# Sheet1.net
KiCad netlist of a schematic drawn in Altium Designer
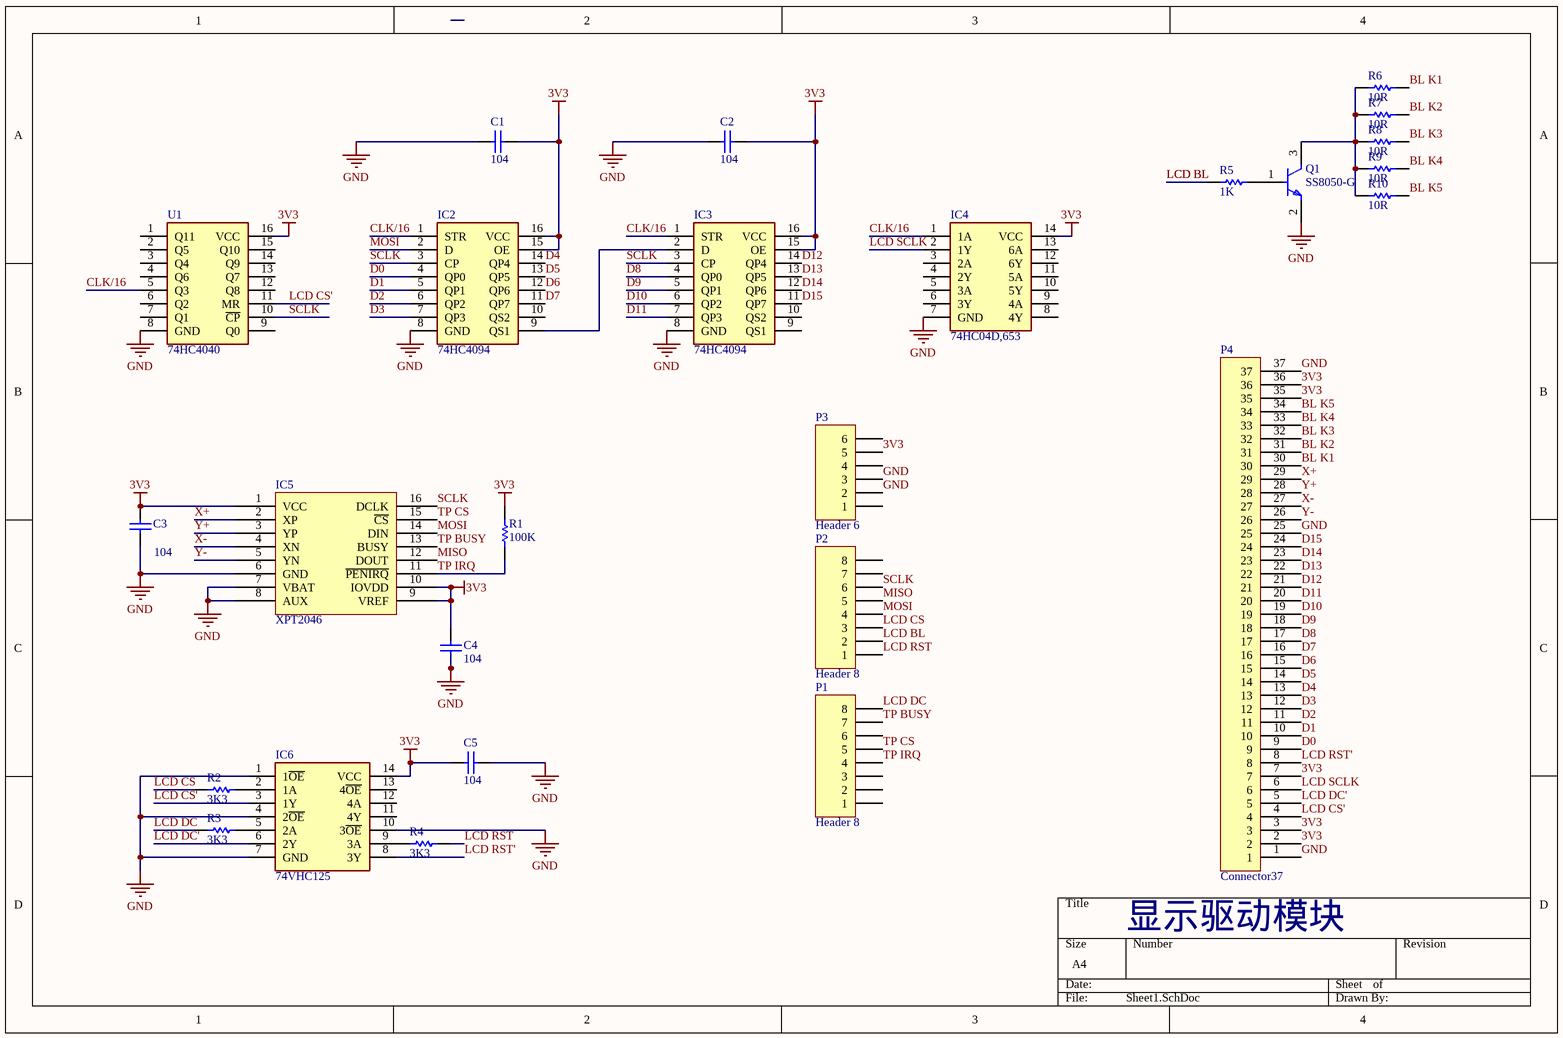
[diagram p0: Sheet1.SchDoc]

(export (version "E")
  (design (tool "Eeschema 10.0.6"))
  (components
    (comp (ref "C1")
      (value "104")
      (footprint "CAPC2013X135X45LL10T25")
      (fields (field (name "MANUFACTURER") "Murata") (field (name "PART NUMBER") "GRM21BR72E103KW03L"))
      (libsource (lib "Altium Content Vault") (part "CAP"))
    )
    (comp (ref "C2")
      (value "104")
      (footprint "CAPC2013X135X45LL10T25")
      (fields (field (name "MANUFACTURER") "Murata") (field (name "PART NUMBER") "GRM21BR72E103KW03L"))
      (libsource (lib "Altium Content Vault") (part "CAP"))
    )
    (comp (ref "C3")
      (value "104")
      (footprint "CAPC2013X135X45LL10T25")
      (fields (field (name "MANUFACTURER") "Murata") (field (name "PART NUMBER") "GRM21BR72E103KW03L"))
      (libsource (lib "Altium Content Vault") (part "CAP"))
    )
    (comp (ref "C4")
      (value "104")
      (footprint "CAPC2013X135X45LL10T25")
      (fields (field (name "MANUFACTURER") "Murata") (field (name "PART NUMBER") "GRM21BR72E103KW03L"))
      (libsource (lib "Altium Content Vault") (part "CAP"))
    )
    (comp (ref "C5")
      (value "104")
      (footprint "CAPC2013X135X45LL10T25")
      (fields (field (name "MANUFACTURER") "Murata") (field (name "PART NUMBER") "GRM21BR72E103KW03L"))
      (libsource (lib "Altium Content Vault") (part "CAP"))
    )
    (comp (ref "IC2")
      (value "74HC4094")
      (footprint "SamacSys:74HC4094D653")
      (description "Integrated Circuit")
      (fields
        (field (name "MANUFACTURER_PART_NUMBER") "74HC4094D,653")
        (field (name "MOUSER PART NUMBER") "771-74HC4094D-T")
      )
      (libsource (lib "*") (part "74HC4094D,653"))
    )
    (comp (ref "IC3")
      (value "74HC4094")
      (footprint "SamacSys:74HC4094D653")
      (description "Integrated Circuit")
      (fields
        (field (name "MANUFACTURER_PART_NUMBER") "74HC4094D,653")
        (field (name "MOUSER PART NUMBER") "771-74HC4094D-T")
      )
      (libsource (lib "*") (part "74HC4094D,653"))
    )
    (comp (ref "IC4")
      (value "74HC04D,653")
      (footprint "SamacSys:SOIC127P600X175-14N")
      (description "Integrated Circuit")
      (fields (field (name "MOUSER PART NUMBER") "771-74HC04D-T"))
      (libsource (lib "*") (part "74HC04D,653"))
    )
    (comp (ref "IC5")
      (value "XPT2046")
      (footprint "TSOP65P640X110-16N")
      (libsource (lib "Schlib1") (part "XPT2046"))
    )
    (comp (ref "IC6")
      (value "74VHC125")
      (footprint "SOP65P640X510-14N")
      (description "Integrated Circuit")
      (fields
        (field (name "MANUFACTURER_PART_NUMBER") "74VHC125D,118")
        (field (name "MOUSER PART NUMBER") "771-74VHC125D118")
      )
      (libsource (lib "*") (part "74VHC125D,118"))
    )
    (comp (ref "P1")
      (value "Header 8")
      (footprint "HDR1X8")
      (description "Header, 8-Pin")
      (fields (field (name "PUBLISHER") "Altium Limited"))
      (libsource (lib "Miscellaneous Connectors") (part "Header 8"))
    )
    (comp (ref "P2")
      (value "Header 8")
      (footprint "HDR1X8")
      (description "Header, 8-Pin")
      (fields (field (name "PUBLISHER") "Altium Limited"))
      (libsource (lib "Miscellaneous Connectors") (part "Header 8"))
    )
    (comp (ref "P3")
      (value "Header 6")
      (footprint "HDR1X6")
      (description "Header, 6-Pin")
      (fields (field (name "PUBLISHER") "Altium Limited"))
      (libsource (lib "Miscellaneous Connectors") (part "Header 6"))
    )
    (comp (ref "P4") (value "Connector37") (footprint "C37") (libsource (lib "Schlib1") (part "Connector37")))
    (comp (ref "Q1")
      (value "SS8050-G")
      (footprint "FP-SS8050-G-MFG")
      (description "NPN TRANSISTOR 1.5A 40V SOT-23 R")
      (libsource (lib "Altium Content Vault") (part "2a1388f82443b098dcd57d24ac7632d"))
    )
    (comp (ref "R1")
      (value "100K")
      (footprint "RESC2013X60X35ML10T20")
      (description "Chip Resistor, 100 KOhm, +/- 1%, 0.125 W, -55 to 155 degC, 0805 (2012 Metric), RoHS, Tape and Reel")
      (fields (field (name "MANUFACTURER") "Yageo") (field (name "TOLERANCE") "1%"))
      (libsource (lib "Altium Content Vault") (part "RES-2"))
    )
    (comp (ref "R2")
      (value "3K3")
      (footprint "RESC2013X60X35ML10T20")
      (description "Chip Resistor, 1 KOhm, +/- 1%, 125 mW, -55 to 155 degC, 0805 (2012 Metric), RoHS, Tape and Reel")
      (fields (field (name "TOLERANCE") "1%") (field (name "MANUFACTURER") "Yageo"))
      (libsource (lib "Altium Content Vault") (part "RES-2"))
    )
    (comp (ref "R3")
      (value "3K3")
      (footprint "RESC2013X60X35ML10T20")
      (description "Chip Resistor, 1 KOhm, +/- 1%, 125 mW, -55 to 155 degC, 0805 (2012 Metric), RoHS, Tape and Reel")
      (fields (field (name "TOLERANCE") "1%") (field (name "MANUFACTURER") "Yageo"))
      (libsource (lib "Altium Content Vault") (part "RES-2"))
    )
    (comp (ref "R4")
      (value "3K3")
      (footprint "RESC2013X60X35ML10T20")
      (description "Chip Resistor, 1 KOhm, +/- 1%, 125 mW, -55 to 155 degC, 0805 (2012 Metric), RoHS, Tape and Reel")
      (fields (field (name "TOLERANCE") "1%") (field (name "MANUFACTURER") "Yageo"))
      (libsource (lib "Altium Content Vault") (part "RES-2"))
    )
    (comp (ref "R5")
      (value "1K")
      (footprint "RESC2013X60X35ML10T20")
      (description "Chip Resistor, 1 KOhm, +/- 1%, 125 mW, -55 to 155 degC, 0805 (2012 Metric), RoHS, Tape and Reel")
      (fields (field (name "TOLERANCE") "1%") (field (name "MANUFACTURER") "Yageo"))
      (libsource (lib "Altium Content Vault") (part "RES-2"))
    )
    (comp (ref "R6")
      (value "10R")
      (footprint "RESC2013X60X35ML10T20")
      (description "Chip Resistor, 10 Ohm, +/- 1%, 0.125 W, -55 to 155 degC, 0805 (2012 Metric), RoHS, Tape and Reel")
      (fields (field (name "MANUFACTURER") "Yageo") (field (name "TOLERANCE") "1%"))
      (libsource (lib "Altium Content Vault") (part "RES-2"))
    )
    (comp (ref "R7")
      (value "10R")
      (footprint "RESC2013X60X35ML10T20")
      (description "Chip Resistor, 10 Ohm, +/- 1%, 0.125 W, -55 to 155 degC, 0805 (2012 Metric), RoHS, Tape and Reel")
      (fields (field (name "MANUFACTURER") "Yageo") (field (name "TOLERANCE") "1%"))
      (libsource (lib "Altium Content Vault") (part "RES-2"))
    )
    (comp (ref "R8")
      (value "10R")
      (footprint "RESC2013X60X35ML10T20")
      (description "Chip Resistor, 10 Ohm, +/- 1%, 0.125 W, -55 to 155 degC, 0805 (2012 Metric), RoHS, Tape and Reel")
      (fields (field (name "MANUFACTURER") "Yageo") (field (name "TOLERANCE") "1%"))
      (libsource (lib "Altium Content Vault") (part "RES-2"))
    )
    (comp (ref "R9")
      (value "10R")
      (footprint "RESC2013X60X35ML10T20")
      (description "Chip Resistor, 10 Ohm, +/- 1%, 0.125 W, -55 to 155 degC, 0805 (2012 Metric), RoHS, Tape and Reel")
      (fields (field (name "MANUFACTURER") "Yageo") (field (name "TOLERANCE") "1%"))
      (libsource (lib "Altium Content Vault") (part "RES-2"))
    )
    (comp (ref "R10")
      (value "10R")
      (footprint "RESC2013X60X35ML10T20")
      (description "Chip Resistor, 10 Ohm, +/- 1%, 0.125 W, -55 to 155 degC, 0805 (2012 Metric), RoHS, Tape and Reel")
      (fields (field (name "MANUFACTURER") "Yageo") (field (name "TOLERANCE") "1%"))
      (libsource (lib "Altium Content Vault") (part "RES-2"))
    )
    (comp (ref "U1")
      (value "74HC4040")
      (footprint "SamacSys:74HC4040D653")
      (description "Integrated Circuit")
      (fields
        (field (name "MANUFACTURER_PART_NUMBER") "74HC4040D,653")
        (field (name "MOUSER PART NUMBER") "771-74HC4040D-T")
      )
      (libsource (lib "*") (part "74HC4040D,653"))
    )
  )
  (nets
    (net (code "1") (name "/BL K1") (class "Default")
      (node (ref "P4") (pin "30") (pinfunction "30_30") (pintype "open_emitter"))
      (node (ref "R6") (pin "2") (pinfunction "2_2") (pintype "passive"))
    )
    (net (code "2") (name "/BL K2") (class "Default")
      (node (ref "P4") (pin "31") (pinfunction "31_31") (pintype "open_emitter"))
      (node (ref "R7") (pin "2") (pinfunction "2_2") (pintype "passive"))
    )
    (net (code "3") (name "/BL K3") (class "Default")
      (node (ref "P4") (pin "32") (pinfunction "32_32") (pintype "open_emitter"))
      (node (ref "R8") (pin "2") (pinfunction "2_2") (pintype "passive"))
    )
    (net (code "4") (name "/BL K4") (class "Default")
      (node (ref "P4") (pin "33") (pinfunction "33_33") (pintype "open_emitter"))
      (node (ref "R9") (pin "2") (pinfunction "2_2") (pintype "passive"))
    )
    (net (code "5") (name "/BL K5") (class "Default")
      (node (ref "P4") (pin "34") (pinfunction "34_34") (pintype "open_emitter"))
      (node (ref "R10") (pin "2") (pinfunction "2_2") (pintype "passive"))
    )
    (net (code "6") (name "/CLK{slash}16") (class "Default")
      (node (ref "IC2") (pin "1") (pinfunction "STR_1") (pintype "passive"))
      (node (ref "IC3") (pin "1") (pinfunction "STR_1") (pintype "passive"))
      (node (ref "IC4") (pin "1") (pinfunction "1A_1") (pintype "passive"))
      (node (ref "U1") (pin "5") (pinfunction "Q3_5") (pintype "passive"))
    )
    (net (code "7") (name "/D0") (class "Default")
      (node (ref "IC2") (pin "4") (pinfunction "QP0_4") (pintype "passive"))
      (node (ref "P4") (pin "9") (pinfunction "9_9") (pintype "open_emitter"))
    )
    (net (code "8") (name "/D1") (class "Default")
      (node (ref "IC2") (pin "5") (pinfunction "QP1_5") (pintype "passive"))
      (node (ref "P4") (pin "10") (pinfunction "10_10") (pintype "open_emitter"))
    )
    (net (code "9") (name "/D2") (class "Default")
      (node (ref "IC2") (pin "6") (pinfunction "QP2_6") (pintype "passive"))
      (node (ref "P4") (pin "11") (pinfunction "11_11") (pintype "open_emitter"))
    )
    (net (code "10") (name "/D3") (class "Default")
      (node (ref "IC2") (pin "7") (pinfunction "QP3_7") (pintype "passive"))
      (node (ref "P4") (pin "12") (pinfunction "12_12") (pintype "open_emitter"))
    )
    (net (code "11") (name "/D4") (class "Default")
      (node (ref "IC2") (pin "14") (pinfunction "QP4_14") (pintype "passive"))
      (node (ref "P4") (pin "13") (pinfunction "13_13") (pintype "open_emitter"))
    )
    (net (code "12") (name "/D5") (class "Default")
      (node (ref "IC2") (pin "13") (pinfunction "QP5_13") (pintype "passive"))
      (node (ref "P4") (pin "14") (pinfunction "14_14") (pintype "open_emitter"))
    )
    (net (code "13") (name "/D6") (class "Default")
      (node (ref "IC2") (pin "12") (pinfunction "QP6_12") (pintype "passive"))
      (node (ref "P4") (pin "15") (pinfunction "15_15") (pintype "open_emitter"))
    )
    (net (code "14") (name "/D7") (class "Default")
      (node (ref "IC2") (pin "11") (pinfunction "QP7_11") (pintype "passive"))
      (node (ref "P4") (pin "16") (pinfunction "16_16") (pintype "open_emitter"))
    )
    (net (code "15") (name "/D8") (class "Default")
      (node (ref "IC3") (pin "4") (pinfunction "QP0_4") (pintype "passive"))
      (node (ref "P4") (pin "17") (pinfunction "17_17") (pintype "open_emitter"))
    )
    (net (code "16") (name "/D9") (class "Default")
      (node (ref "IC3") (pin "5") (pinfunction "QP1_5") (pintype "passive"))
      (node (ref "P4") (pin "18") (pinfunction "18_18") (pintype "open_emitter"))
    )
    (net (code "17") (name "/D10") (class "Default")
      (node (ref "IC3") (pin "6") (pinfunction "QP2_6") (pintype "passive"))
      (node (ref "P4") (pin "19") (pinfunction "19_19") (pintype "open_emitter"))
    )
    (net (code "18") (name "/D11") (class "Default")
      (node (ref "IC3") (pin "7") (pinfunction "QP3_7") (pintype "passive"))
      (node (ref "P4") (pin "20") (pinfunction "20_20") (pintype "open_emitter"))
    )
    (net (code "19") (name "/D12") (class "Default")
      (node (ref "IC3") (pin "14") (pinfunction "QP4_14") (pintype "passive"))
      (node (ref "P4") (pin "21") (pinfunction "21_21") (pintype "open_emitter"))
    )
    (net (code "20") (name "/D13") (class "Default")
      (node (ref "IC3") (pin "13") (pinfunction "QP5_13") (pintype "passive"))
      (node (ref "P4") (pin "22") (pinfunction "22_22") (pintype "open_emitter"))
    )
    (net (code "21") (name "/D14") (class "Default")
      (node (ref "IC3") (pin "12") (pinfunction "QP6_12") (pintype "passive"))
      (node (ref "P4") (pin "23") (pinfunction "23_23") (pintype "open_emitter"))
    )
    (net (code "22") (name "/D15") (class "Default")
      (node (ref "IC3") (pin "11") (pinfunction "QP7_11") (pintype "passive"))
      (node (ref "P4") (pin "24") (pinfunction "24_24") (pintype "open_emitter"))
    )
    (net (code "23") (name "/LCD BL") (class "Default")
      (node (ref "P2") (pin "2") (pinfunction "2_2") (pintype "passive"))
      (node (ref "R5") (pin "1") (pinfunction "1_1") (pintype "passive"))
    )
    (net (code "24") (name "/LCD CS") (class "Default")
      (node (ref "P2") (pin "3") (pinfunction "3_3") (pintype "passive"))
      (node (ref "R2") (pin "1") (pinfunction "1_1") (pintype "passive"))
    )
    (net (code "25") (name "/LCD CS'") (class "Default")
      (node (ref "IC6") (pin "3") (pinfunction "1Y_3") (pintype "passive"))
      (node (ref "P4") (pin "4") (pinfunction "4_4") (pintype "open_emitter"))
      (node (ref "U1") (pin "11") (pinfunction "MR_11") (pintype "passive"))
    )
    (net (code "26") (name "/LCD DC") (class "Default")
      (node (ref "P1") (pin "8") (pinfunction "8_8") (pintype "passive"))
      (node (ref "R3") (pin "1") (pinfunction "1_1") (pintype "passive"))
    )
    (net (code "27") (name "/LCD DC'") (class "Default")
      (node (ref "IC6") (pin "6") (pinfunction "2Y_6") (pintype "passive"))
      (node (ref "P4") (pin "5") (pinfunction "5_5") (pintype "open_emitter"))
    )
    (net (code "28") (name "/LCD RST") (class "Default")
      (node (ref "P2") (pin "1") (pinfunction "1_1") (pintype "passive"))
      (node (ref "R4") (pin "2") (pinfunction "2_2") (pintype "passive"))
    )
    (net (code "29") (name "/LCD RST'") (class "Default")
      (node (ref "IC6") (pin "8") (pinfunction "3Y_8") (pintype "passive"))
      (node (ref "P4") (pin "8") (pinfunction "8_8") (pintype "open_emitter"))
    )
    (net (code "30") (name "/LCD SCLK") (class "Default")
      (node (ref "IC4") (pin "2") (pinfunction "1Y_2") (pintype "passive"))
      (node (ref "P4") (pin "6") (pinfunction "6_6") (pintype "open_emitter"))
    )
    (net (code "31") (name "/MISO") (class "Default")
      (node (ref "IC5") (pin "12") (pinfunction "DOUT_12") (pintype "open_emitter"))
      (node (ref "P2") (pin "5") (pinfunction "5_5") (pintype "passive"))
    )
    (net (code "32") (name "/MOSI") (class "Default")
      (node (ref "IC2") (pin "2") (pinfunction "D_2") (pintype "passive"))
      (node (ref "IC5") (pin "14") (pinfunction "DIN_14") (pintype "open_emitter"))
      (node (ref "P2") (pin "4") (pinfunction "4_4") (pintype "passive"))
    )
    (net (code "33") (name "/SCLK") (class "Default")
      (node (ref "IC2") (pin "3") (pinfunction "CP_3") (pintype "passive"))
      (node (ref "IC3") (pin "3") (pinfunction "CP_3") (pintype "passive"))
      (node (ref "IC5") (pin "16") (pinfunction "DCLK_16") (pintype "open_emitter"))
      (node (ref "P2") (pin "6") (pinfunction "6_6") (pintype "passive"))
      (node (ref "U1") (pin "10") (pinfunction "~{CP}_10") (pintype "passive"))
    )
    (net (code "34") (name "/TP BUSY") (class "Default")
      (node (ref "IC5") (pin "13") (pinfunction "BUSY_13") (pintype "open_emitter"))
      (node (ref "P1") (pin "7") (pinfunction "7_7") (pintype "passive"))
    )
    (net (code "35") (name "/TP CS") (class "Default")
      (node (ref "IC5") (pin "15") (pinfunction "~{CS}_15") (pintype "open_emitter"))
      (node (ref "P1") (pin "5") (pinfunction "5_5") (pintype "passive"))
    )
    (net (code "36") (name "/TP IRQ") (class "Default")
      (node (ref "IC5") (pin "11") (pinfunction "~{PENIRQ}_11") (pintype "open_emitter"))
      (node (ref "P1") (pin "4") (pinfunction "4_4") (pintype "passive"))
      (node (ref "R1") (pin "2") (pinfunction "2_2") (pintype "passive"))
    )
    (net (code "37") (name "/X+") (class "Default")
      (node (ref "IC5") (pin "2") (pinfunction "XP_2") (pintype "open_emitter"))
      (node (ref "P4") (pin "29") (pinfunction "29_29") (pintype "open_emitter"))
    )
    (net (code "38") (name "/X-") (class "Default")
      (node (ref "IC5") (pin "4") (pinfunction "XN_4") (pintype "open_emitter"))
      (node (ref "P4") (pin "27") (pinfunction "27_27") (pintype "open_emitter"))
    )
    (net (code "39") (name "/Y+") (class "Default")
      (node (ref "IC5") (pin "3") (pinfunction "YP_3") (pintype "open_emitter"))
      (node (ref "P4") (pin "28") (pinfunction "28_28") (pintype "open_emitter"))
    )
    (net (code "40") (name "/Y-") (class "Default")
      (node (ref "IC5") (pin "5") (pinfunction "YN_5") (pintype "open_emitter"))
      (node (ref "P4") (pin "26") (pinfunction "26_26") (pintype "open_emitter"))
    )
    (net (code "41") (name "3V3") (class "Default")
      (node (ref "C1") (pin "2") (pinfunction "2_2") (pintype "passive"))
      (node (ref "C2") (pin "2") (pinfunction "2_2") (pintype "passive"))
      (node (ref "C3") (pin "1") (pinfunction "1_1") (pintype "passive"))
      (node (ref "C4") (pin "1") (pinfunction "1_1") (pintype "passive"))
      (node (ref "C5") (pin "1") (pinfunction "1_1") (pintype "passive"))
      (node (ref "IC2") (pin "15") (pinfunction "OE_15") (pintype "passive"))
      (node (ref "IC2") (pin "16") (pinfunction "VCC_16") (pintype "passive"))
      (node (ref "IC3") (pin "15") (pinfunction "OE_15") (pintype "passive"))
      (node (ref "IC3") (pin "16") (pinfunction "VCC_16") (pintype "passive"))
      (node (ref "IC4") (pin "14") (pinfunction "VCC_14") (pintype "passive"))
      (node (ref "IC5") (pin "1") (pinfunction "VCC_1") (pintype "open_emitter"))
      (node (ref "IC5") (pin "10") (pinfunction "IOVDD_10") (pintype "open_emitter"))
      (node (ref "IC5") (pin "9") (pinfunction "VREF_9") (pintype "open_emitter"))
      (node (ref "IC6") (pin "14") (pinfunction "VCC_14") (pintype "passive"))
      (node (ref "P3") (pin "5") (pinfunction "5_5") (pintype "passive"))
      (node (ref "P4") (pin "2") (pinfunction "2_2") (pintype "open_emitter"))
      (node (ref "P4") (pin "3") (pinfunction "3_3") (pintype "open_emitter"))
      (node (ref "P4") (pin "35") (pinfunction "35_35") (pintype "open_emitter"))
      (node (ref "P4") (pin "36") (pinfunction "36_36") (pintype "open_emitter"))
      (node (ref "P4") (pin "7") (pinfunction "7_7") (pintype "open_emitter"))
      (node (ref "R1") (pin "1") (pinfunction "1_1") (pintype "passive"))
      (node (ref "U1") (pin "16") (pinfunction "VCC_16") (pintype "passive"))
    )
    (net (code "42") (name "GND") (class "Default")
      (node (ref "C1") (pin "1") (pinfunction "1_1") (pintype "passive"))
      (node (ref "C2") (pin "1") (pinfunction "1_1") (pintype "passive"))
      (node (ref "C3") (pin "2") (pinfunction "2_2") (pintype "passive"))
      (node (ref "C4") (pin "2") (pinfunction "2_2") (pintype "passive"))
      (node (ref "C5") (pin "2") (pinfunction "2_2") (pintype "passive"))
      (node (ref "IC2") (pin "8") (pinfunction "GND_8") (pintype "passive"))
      (node (ref "IC3") (pin "8") (pinfunction "GND_8") (pintype "passive"))
      (node (ref "IC4") (pin "7") (pinfunction "GND_7") (pintype "passive"))
      (node (ref "IC5") (pin "6") (pinfunction "GND_6") (pintype "open_emitter"))
      (node (ref "IC5") (pin "7") (pinfunction "VBAT_7") (pintype "open_emitter"))
      (node (ref "IC5") (pin "8") (pinfunction "AUX_8") (pintype "open_emitter"))
      (node (ref "IC6") (pin "1") (pinfunction "1~{OE}_1") (pintype "passive"))
      (node (ref "IC6") (pin "10") (pinfunction "3~{OE}_10") (pintype "passive"))
      (node (ref "IC6") (pin "4") (pinfunction "2~{OE}_4") (pintype "passive"))
      (node (ref "IC6") (pin "7") (pinfunction "GND_7") (pintype "passive"))
      (node (ref "P3") (pin "2") (pinfunction "2_2") (pintype "passive"))
      (node (ref "P3") (pin "3") (pinfunction "3_3") (pintype "passive"))
      (node (ref "P4") (pin "1") (pinfunction "1_1") (pintype "open_emitter"))
      (node (ref "P4") (pin "25") (pinfunction "25_25") (pintype "open_emitter"))
      (node (ref "P4") (pin "37") (pinfunction "37_37") (pintype "open_emitter"))
      (node (ref "Q1") (pin "2") (pinfunction "E_2") (pintype "passive"))
      (node (ref "U1") (pin "8") (pinfunction "GND_8") (pintype "passive"))
    )
    (net (code "43") (name "Net-(IC2-QS1)") (class "Default")
      (node (ref "IC2") (pin "9") (pinfunction "QS1_9") (pintype "passive"))
      (node (ref "IC3") (pin "2") (pinfunction "D_2") (pintype "passive"))
    )
    (net (code "44") (name "Net-(IC6-1A)") (class "Default")
      (node (ref "IC6") (pin "2") (pinfunction "1A_2") (pintype "passive"))
      (node (ref "R2") (pin "2") (pinfunction "2_2") (pintype "passive"))
    )
    (net (code "45") (name "Net-(IC6-2A)") (class "Default")
      (node (ref "IC6") (pin "5") (pinfunction "2A_5") (pintype "passive"))
      (node (ref "R3") (pin "2") (pinfunction "2_2") (pintype "passive"))
    )
    (net (code "46") (name "Net-(IC6-3A)") (class "Default")
      (node (ref "IC6") (pin "9") (pinfunction "3A_9") (pintype "passive"))
      (node (ref "R4") (pin "1") (pinfunction "1_1") (pintype "passive"))
    )
    (net (code "47") (name "Net-(Q1-B)") (class "Default")
      (node (ref "Q1") (pin "1") (pinfunction "B_1") (pintype "passive"))
      (node (ref "R5") (pin "2") (pinfunction "2_2") (pintype "passive"))
    )
    (net (code "48") (name "Net-(Q1-C)") (class "Default")
      (node (ref "Q1") (pin "3") (pinfunction "C_3") (pintype "passive"))
      (node (ref "R10") (pin "1") (pinfunction "1_1") (pintype "passive"))
      (node (ref "R6") (pin "1") (pinfunction "1_1") (pintype "passive"))
      (node (ref "R7") (pin "1") (pinfunction "1_1") (pintype "passive"))
      (node (ref "R8") (pin "1") (pinfunction "1_1") (pintype "passive"))
      (node (ref "R9") (pin "1") (pinfunction "1_1") (pintype "passive"))
    )
    (net (code "49") (name "unconnected-(IC2-QS2-Pad10)") (class "Default")
      (node (ref "IC2") (pin "10") (pinfunction "QS2_10") (pintype "passive"))
    )
    (net (code "50") (name "unconnected-(IC3-QS1-Pad9)") (class "Default")
      (node (ref "IC3") (pin "9") (pinfunction "QS1_9") (pintype "passive"))
    )
    (net (code "51") (name "unconnected-(IC3-QS2-Pad10)") (class "Default")
      (node (ref "IC3") (pin "10") (pinfunction "QS2_10") (pintype "passive"))
    )
    (net (code "52") (name "unconnected-(IC4-2A-Pad3)") (class "Default")
      (node (ref "IC4") (pin "3") (pinfunction "2A_3") (pintype "passive"))
    )
    (net (code "53") (name "unconnected-(IC4-2Y-Pad4)") (class "Default")
      (node (ref "IC4") (pin "4") (pinfunction "2Y_4") (pintype "passive"))
    )
    (net (code "54") (name "unconnected-(IC4-3A-Pad5)") (class "Default")
      (node (ref "IC4") (pin "5") (pinfunction "3A_5") (pintype "passive"))
    )
    (net (code "55") (name "unconnected-(IC4-3Y-Pad6)") (class "Default")
      (node (ref "IC4") (pin "6") (pinfunction "3Y_6") (pintype "passive"))
    )
    (net (code "56") (name "unconnected-(IC4-4A-Pad9)") (class "Default")
      (node (ref "IC4") (pin "9") (pinfunction "4A_9") (pintype "passive"))
    )
    (net (code "57") (name "unconnected-(IC4-4Y-Pad8)") (class "Default")
      (node (ref "IC4") (pin "8") (pinfunction "4Y_8") (pintype "passive"))
    )
    (net (code "58") (name "unconnected-(IC4-5A-Pad11)") (class "Default")
      (node (ref "IC4") (pin "11") (pinfunction "5A_11") (pintype "passive"))
    )
    (net (code "59") (name "unconnected-(IC4-5Y-Pad10)") (class "Default")
      (node (ref "IC4") (pin "10") (pinfunction "5Y_10") (pintype "passive"))
    )
    (net (code "60") (name "unconnected-(IC4-6A-Pad13)") (class "Default")
      (node (ref "IC4") (pin "13") (pinfunction "6A_13") (pintype "passive"))
    )
    (net (code "61") (name "unconnected-(IC4-6Y-Pad12)") (class "Default")
      (node (ref "IC4") (pin "12") (pinfunction "6Y_12") (pintype "passive"))
    )
    (net (code "62") (name "unconnected-(IC6-4A-Pad12)") (class "Default")
      (node (ref "IC6") (pin "12") (pinfunction "4A_12") (pintype "passive"))
    )
    (net (code "63") (name "unconnected-(IC6-4Y-Pad11)") (class "Default")
      (node (ref "IC6") (pin "11") (pinfunction "4Y_11") (pintype "passive"))
    )
    (net (code "64") (name "unconnected-(IC6-4~{OE}-Pad13)") (class "Default")
      (node (ref "IC6") (pin "13") (pinfunction "4~{OE}_13") (pintype "passive"))
    )
    (net (code "65") (name "unconnected-(P1-Pad1)") (class "Default")
      (node (ref "P1") (pin "1") (pinfunction "1_1") (pintype "passive"))
    )
    (net (code "66") (name "unconnected-(P1-Pad2)") (class "Default")
      (node (ref "P1") (pin "2") (pinfunction "2_2") (pintype "passive"))
    )
    (net (code "67") (name "unconnected-(P1-Pad3)") (class "Default")
      (node (ref "P1") (pin "3") (pinfunction "3_3") (pintype "passive"))
    )
    (net (code "68") (name "unconnected-(P1-Pad6)") (class "Default")
      (node (ref "P1") (pin "6") (pinfunction "6_6") (pintype "passive"))
    )
    (net (code "69") (name "unconnected-(P2-Pad7)") (class "Default")
      (node (ref "P2") (pin "7") (pinfunction "7_7") (pintype "passive"))
    )
    (net (code "70") (name "unconnected-(P2-Pad8)") (class "Default")
      (node (ref "P2") (pin "8") (pinfunction "8_8") (pintype "passive"))
    )
    (net (code "71") (name "unconnected-(P3-Pad1)") (class "Default")
      (node (ref "P3") (pin "1") (pinfunction "1_1") (pintype "passive"))
    )
    (net (code "72") (name "unconnected-(P3-Pad4)") (class "Default")
      (node (ref "P3") (pin "4") (pinfunction "4_4") (pintype "passive"))
    )
    (net (code "73") (name "unconnected-(P3-Pad6)") (class "Default")
      (node (ref "P3") (pin "6") (pinfunction "6_6") (pintype "passive"))
    )
    (net (code "74") (name "unconnected-(U1-Q0-Pad9)") (class "Default")
      (node (ref "U1") (pin "9") (pinfunction "Q0_9") (pintype "passive"))
    )
    (net (code "75") (name "unconnected-(U1-Q1-Pad7)") (class "Default")
      (node (ref "U1") (pin "7") (pinfunction "Q1_7") (pintype "passive"))
    )
    (net (code "76") (name "unconnected-(U1-Q2-Pad6)") (class "Default")
      (node (ref "U1") (pin "6") (pinfunction "Q2_6") (pintype "passive"))
    )
    (net (code "77") (name "unconnected-(U1-Q4-Pad3)") (class "Default")
      (node (ref "U1") (pin "3") (pinfunction "Q4_3") (pintype "passive"))
    )
    (net (code "78") (name "unconnected-(U1-Q5-Pad2)") (class "Default")
      (node (ref "U1") (pin "2") (pinfunction "Q5_2") (pintype "passive"))
    )
    (net (code "79") (name "unconnected-(U1-Q6-Pad4)") (class "Default")
      (node (ref "U1") (pin "4") (pinfunction "Q6_4") (pintype "passive"))
    )
    (net (code "80") (name "unconnected-(U1-Q7-Pad13)") (class "Default")
      (node (ref "U1") (pin "13") (pinfunction "Q7_13") (pintype "passive"))
    )
    (net (code "81") (name "unconnected-(U1-Q8-Pad12)") (class "Default")
      (node (ref "U1") (pin "12") (pinfunction "Q8_12") (pintype "passive"))
    )
    (net (code "82") (name "unconnected-(U1-Q9-Pad14)") (class "Default")
      (node (ref "U1") (pin "14") (pinfunction "Q9_14") (pintype "passive"))
    )
    (net (code "83") (name "unconnected-(U1-Q10-Pad15)") (class "Default")
      (node (ref "U1") (pin "15") (pinfunction "Q10_15") (pintype "passive"))
    )
    (net (code "84") (name "unconnected-(U1-Q11-Pad1)") (class "Default")
      (node (ref "U1") (pin "1") (pinfunction "Q11_1") (pintype "passive"))
    )
  )
)
